# main_board_schematic.net
KiCad netlist of a schematic drawn in EasyEDA
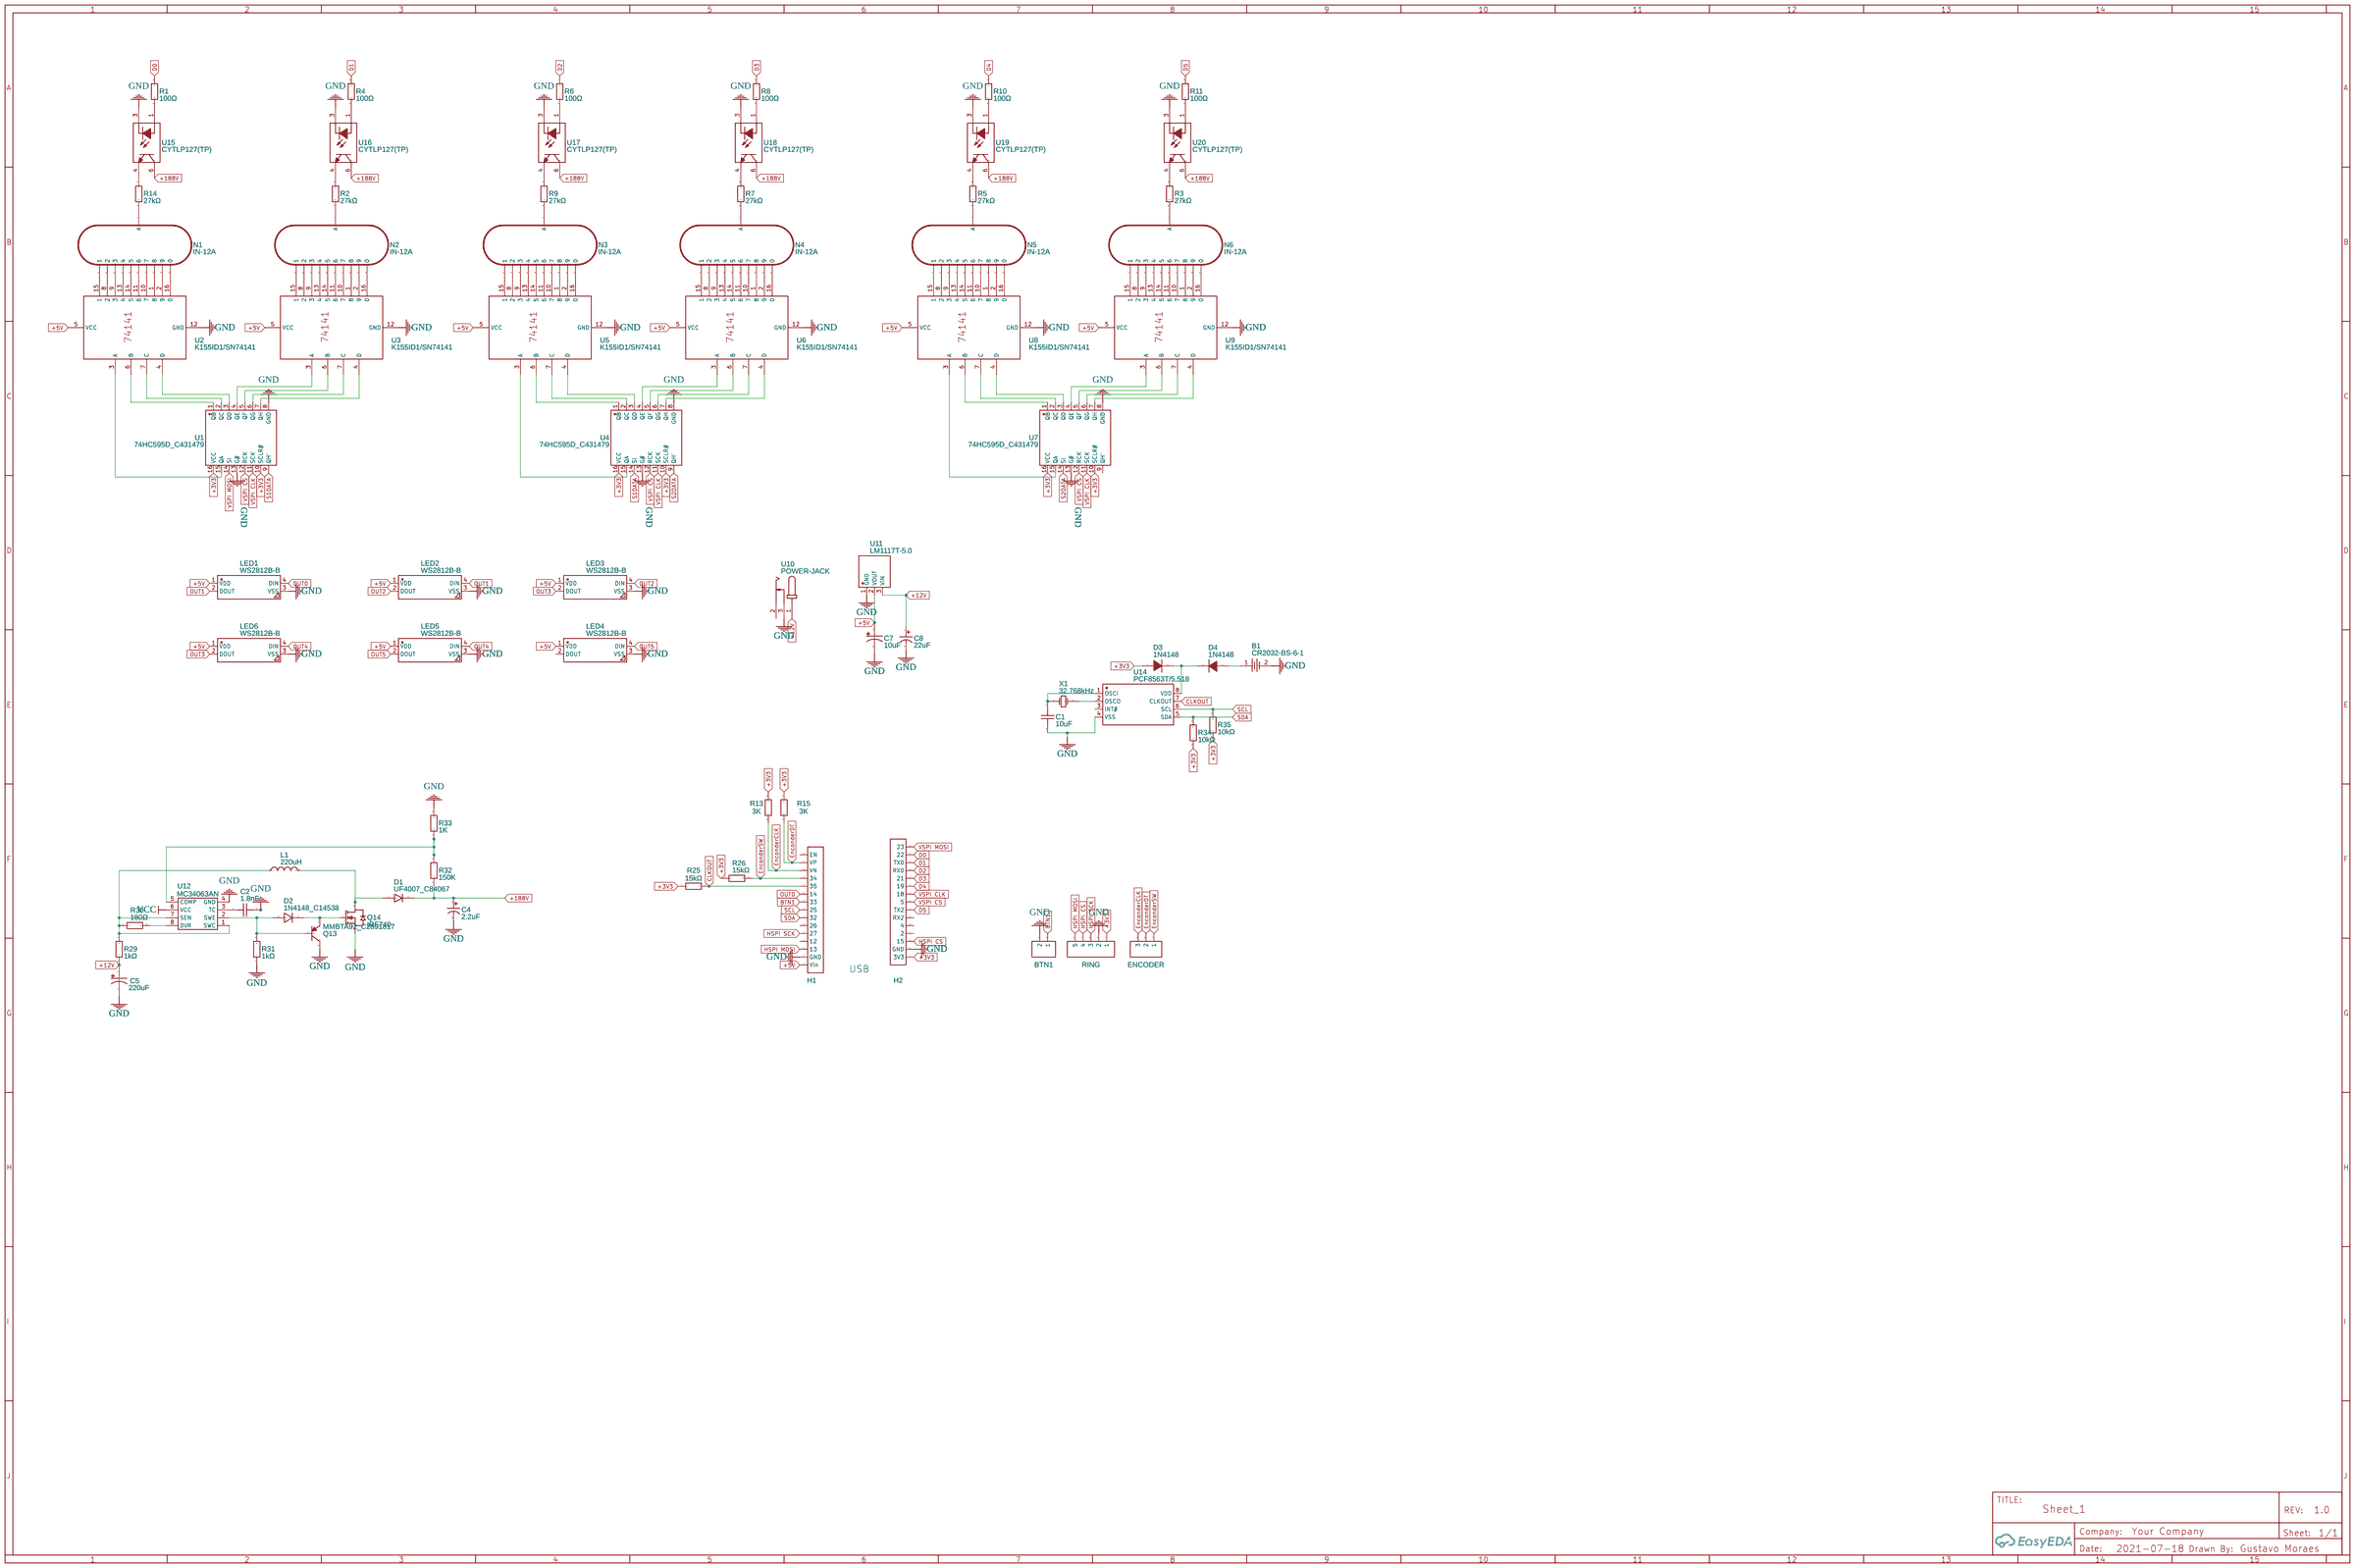
[diagram p0: schematic sheet]

(export (version "E")
  (design (tool "Eeschema 10.0.6"))
  (components
    (comp (ref "B1")
      (value "CR2032-BS-6-1")
      (fields (field (name "BOM_Supplier Part") "C70377"))
      (libsource (lib "") (part "CR2032-BS-6-1"))
    )
    (comp (ref "BTN1")
      (value "HDR-M-2.54_1x2")
      (fields (field (name "BOM_Supplier Part") "C124375"))
      (libsource (lib "") (part "HDR-M-2.54_1x2"))
    )
    (comp (ref "C1")
      (value "10uF")
      (fields
        (field (name "BOM_Manufacturer Part") "C0603X5R106K6R3NT")
        (field (name "BOM_Supplier Part") "C475250")
      )
      (libsource (lib "") (part "C0603X5R106K6R3NT"))
    )
    (comp (ref "C2")
      (value "1.8nF")
      (fields
        (field (name "BOM_Manufacturer Part") "NV1206B182K102CEDN")
        (field (name "BOM_Supplier Part") "C2760344")
      )
      (libsource (lib "") (part "NV1206B182K102CEDN"))
    )
    (comp (ref "C4")
      (value "2.2uF")
      (fields
        (field (name "BOM_Manufacturer Part") "UD2E2R2M0610")
        (field (name "BOM_Supplier Part") "C98559")
      )
      (libsource (lib "") (part "UD2E2R2M0610"))
    )
    (comp (ref "C5")
      (value "220uF")
      (fields
        (field (name "BOM_Manufacturer Part") "RT1E221M0810")
        (field (name "BOM_Supplier Part") "C280403")
      )
      (libsource (lib "") (part "RT1E221M0810"))
    )
    (comp (ref "C7")
      (value "10uF")
      (fields
        (field (name "BOM_Manufacturer Part") "UWX1C100MCL2GB")
        (field (name "BOM_Supplier Part") "C250999")
      )
      (libsource (lib "") (part "UWX1C100MCL2GB"))
    )
    (comp (ref "C8")
      (value "22uF")
      (fields
        (field (name "BOM_Manufacturer Part") "RVT1C220M0405")
        (field (name "BOM_Supplier Part") "C72502")
      )
      (libsource (lib "") (part "RVT1C220M0405"))
    )
    (comp (ref "D1")
      (value "UF4007_C84067")
      (fields (field (name "BOM_Manufacturer Part") "UF4007") (field (name "BOM_Supplier Part") "C84067"))
      (libsource (lib "") (part "UF4007_C84067"))
    )
    (comp (ref "D2")
      (value "1N4148_C14538")
      (fields (field (name "BOM_Manufacturer Part") "1N4148") (field (name "BOM_Supplier Part") "C14538"))
      (libsource (lib "") (part "1N4148_C14538"))
    )
    (comp (ref "D3")
      (value "1N4148")
      (fields (field (name "BOM_Supplier Part") "C14516"))
      (libsource (lib "") (part "1N4148"))
    )
    (comp (ref "D4")
      (value "1N4148")
      (fields (field (name "BOM_Supplier Part") "C14516"))
      (libsource (lib "") (part "1N4148_1"))
    )
    (comp (ref "ENCODER")
      (value "HDR-M-2.54_1x3")
      (fields (field (name "BOM_Supplier Part") "C180248"))
      (libsource (lib "") (part "HDR-M-2.54_1x3"))
    )
    (comp (ref "H1")
      (value "HDR-F-2.54_1x15")
      (fields (field (name "BOM_Supplier Part") "C124408"))
      (libsource (lib "") (part "HDR-F-2.54_1x15"))
    )
    (comp (ref "H2")
      (value "HDR-F-2.54_1x15")
      (fields (field (name "BOM_Supplier Part") "C124408"))
      (libsource (lib "") (part "HDR-F-2.54_1x15_1"))
    )
    (comp (ref "L1")
      (value "220uH")
      (fields
        (field (name "BOM_Manufacturer Part") "SLH1207S221MTT")
        (field (name "BOM_Supplier Part") "C182174")
      )
      (libsource (lib "") (part "SLH1207S221MTT"))
    )
    (comp (ref "LED1")
      (value "WS2812B-B")
      (fields (field (name "BOM_Supplier Part") "C114586"))
      (libsource (lib "") (part "WS2812B-B"))
    )
    (comp (ref "LED2")
      (value "WS2812B-B")
      (fields (field (name "BOM_Supplier Part") "C114586"))
      (libsource (lib "") (part "WS2812B-B"))
    )
    (comp (ref "LED3")
      (value "WS2812B-B")
      (fields (field (name "BOM_Supplier Part") "C114586"))
      (libsource (lib "") (part "WS2812B-B"))
    )
    (comp (ref "LED4")
      (value "WS2812B-B")
      (fields (field (name "BOM_Supplier Part") "C114586"))
      (libsource (lib "") (part "WS2812B-B"))
    )
    (comp (ref "LED5")
      (value "WS2812B-B")
      (fields (field (name "BOM_Supplier Part") "C114586"))
      (libsource (lib "") (part "WS2812B-B"))
    )
    (comp (ref "LED6")
      (value "WS2812B-B")
      (fields (field (name "BOM_Supplier Part") "C114586"))
      (libsource (lib "") (part "WS2812B-B"))
    )
    (comp (ref "N1") (value "IN-12A") (libsource (lib "") (part "IN-12A")))
    (comp (ref "N2") (value "IN-12A") (libsource (lib "") (part "IN-12A")))
    (comp (ref "N3") (value "IN-12A") (libsource (lib "") (part "IN-12A")))
    (comp (ref "N4") (value "IN-12A") (libsource (lib "") (part "IN-12A")))
    (comp (ref "N5") (value "IN-12A") (libsource (lib "") (part "IN-12A")))
    (comp (ref "N6") (value "IN-12A") (libsource (lib "") (part "IN-12A")))
    (comp (ref "Q13")
      (value "MMBTA92_C2891817")
      (fields (field (name "BOM_Manufacturer Part") "MMBTA92") (field (name "BOM_Supplier Part") "C2891817"))
      (libsource (lib "") (part "MMBTA92_C2891817"))
    )
    (comp (ref "Q14")
      (value "IRF740")
      (fields (field (name "BOM_Supplier Part") "C358408"))
      (libsource (lib "") (part "IRF740"))
    )
    (comp (ref "R1")
      (value "100Ω")
      (fields
        (field (name "BOM_Manufacturer Part") "AECR0805F100RK9")
        (field (name "BOM_Supplier Part") "C328380")
      )
      (libsource (lib "") (part "AECR0805F100RK9"))
    )
    (comp (ref "R2")
      (value "27kΩ")
      (fields
        (field (name "BOM_Manufacturer Part") "ARG06FTC2702")
        (field (name "BOM_Supplier Part") "C294144")
      )
      (libsource (lib "") (part "ARG06FTC2702"))
    )
    (comp (ref "R3")
      (value "27kΩ")
      (fields
        (field (name "BOM_Manufacturer Part") "ARG06FTC2702")
        (field (name "BOM_Supplier Part") "C294144")
      )
      (libsource (lib "") (part "ARG06FTC2702"))
    )
    (comp (ref "R4")
      (value "100Ω")
      (fields
        (field (name "BOM_Manufacturer Part") "AECR0805F100RK9")
        (field (name "BOM_Supplier Part") "C328380")
      )
      (libsource (lib "") (part "AECR0805F100RK9"))
    )
    (comp (ref "R5")
      (value "27kΩ")
      (fields
        (field (name "BOM_Manufacturer Part") "ARG06FTC2702")
        (field (name "BOM_Supplier Part") "C294144")
      )
      (libsource (lib "") (part "ARG06FTC2702"))
    )
    (comp (ref "R6")
      (value "100Ω")
      (fields
        (field (name "BOM_Manufacturer Part") "AECR0805F100RK9")
        (field (name "BOM_Supplier Part") "C328380")
      )
      (libsource (lib "") (part "AECR0805F100RK9"))
    )
    (comp (ref "R7")
      (value "27kΩ")
      (fields
        (field (name "BOM_Manufacturer Part") "ARG06FTC2702")
        (field (name "BOM_Supplier Part") "C294144")
      )
      (libsource (lib "") (part "ARG06FTC2702"))
    )
    (comp (ref "R8")
      (value "100Ω")
      (fields
        (field (name "BOM_Manufacturer Part") "AECR0805F100RK9")
        (field (name "BOM_Supplier Part") "C328380")
      )
      (libsource (lib "") (part "AECR0805F100RK9"))
    )
    (comp (ref "R9")
      (value "27kΩ")
      (fields
        (field (name "BOM_Manufacturer Part") "ARG06FTC2702")
        (field (name "BOM_Supplier Part") "C294144")
      )
      (libsource (lib "") (part "ARG06FTC2702"))
    )
    (comp (ref "R10")
      (value "100Ω")
      (fields
        (field (name "BOM_Manufacturer Part") "AECR0805F100RK9")
        (field (name "BOM_Supplier Part") "C328380")
      )
      (libsource (lib "") (part "AECR0805F100RK9"))
    )
    (comp (ref "R11")
      (value "100Ω")
      (fields
        (field (name "BOM_Manufacturer Part") "AECR0805F100RK9")
        (field (name "BOM_Supplier Part") "C328380")
      )
      (libsource (lib "") (part "AECR0805F100RK9"))
    )
    (comp (ref "R13")
      (value "3K")
      (fields
        (field (name "BOM_Manufacturer Part") "RC0805FR-073KL")
        (field (name "BOM_Supplier Part") "C126350")
      )
      (libsource (lib "") (part "RC0805FR-073KL"))
    )
    (comp (ref "R14")
      (value "27kΩ")
      (fields
        (field (name "BOM_Manufacturer Part") "ARG06FTC2702")
        (field (name "BOM_Supplier Part") "C294144")
      )
      (libsource (lib "") (part "ARG06FTC2702"))
    )
    (comp (ref "R15")
      (value "3K")
      (fields
        (field (name "BOM_Manufacturer Part") "RC0805FR-073KL")
        (field (name "BOM_Supplier Part") "C126350")
      )
      (libsource (lib "") (part "RC0805FR-073KL"))
    )
    (comp (ref "R25")
      (value "15kΩ")
      (fields
        (field (name "BOM_Manufacturer Part") "ERJ-6ENF1502V")
        (field (name "BOM_Supplier Part") "C192065")
      )
      (libsource (lib "") (part "ERJ-6ENF1502V"))
    )
    (comp (ref "R26")
      (value "15kΩ")
      (fields
        (field (name "BOM_Manufacturer Part") "ERJ-6ENF1502V")
        (field (name "BOM_Supplier Part") "C192065")
      )
      (libsource (lib "") (part "ERJ-6ENF1502V"))
    )
    (comp (ref "R29")
      (value "1kΩ")
      (fields
        (field (name "BOM_Manufacturer Part") "AECR1206F1K00K9")
        (field (name "BOM_Supplier Part") "C328410")
      )
      (libsource (lib "") (part "AECR1206F1K00K9"))
    )
    (comp (ref "R30")
      (value "180Ω")
      (fields
        (field (name "BOM_Manufacturer Part") "QR1206J180RP05")
        (field (name "BOM_Supplier Part") "C149884")
      )
      (libsource (lib "") (part "QR1206J180RP05"))
    )
    (comp (ref "R31")
      (value "1kΩ")
      (fields
        (field (name "BOM_Manufacturer Part") "AECR1206F1K00K9")
        (field (name "BOM_Supplier Part") "C328410")
      )
      (libsource (lib "") (part "AECR1206F1K00K9"))
    )
    (comp (ref "R32")
      (value "150K")
      (fields
        (field (name "BOM_Manufacturer Part") "MFR0W4F1503A50")
        (field (name "BOM_Supplier Part") "C58618")
      )
      (libsource (lib "") (part "MFR0W4F1503A50"))
    )
    (comp (ref "R33")
      (value "1K")
      (fields
        (field (name "BOM_Manufacturer Part") "MFR0W4F1001A50")
        (field (name "BOM_Supplier Part") "C57435")
      )
      (libsource (lib "") (part "MFR0W4F1001A50"))
    )
    (comp (ref "R34")
      (value "10kΩ")
      (fields
        (field (name "BOM_Manufacturer Part") "WR08X1002FTL")
        (field (name "BOM_Supplier Part") "C108451")
      )
      (libsource (lib "") (part "WR08X1002FTL"))
    )
    (comp (ref "R35")
      (value "10kΩ")
      (fields
        (field (name "BOM_Manufacturer Part") "WR08X1002FTL")
        (field (name "BOM_Supplier Part") "C108451")
      )
      (libsource (lib "") (part "WR08X1002FTL"))
    )
    (comp (ref "RING")
      (value "LED Ring")
      (fields (field (name "BOM_Supplier Part") "C358687"))
      (libsource (lib "") (part "HDR-M-2.54_1x5"))
    )
    (comp (ref "U1")
      (value "74HC595D_C431479")
      (fields (field (name "BOM_Manufacturer Part") "74HC595D") (field (name "BOM_Supplier Part") "C431479"))
      (libsource (lib "") (part "74HC595D_C431479"))
    )
    (comp (ref "U2") (value "K155ID1/SN74141") (libsource (lib "") (part "K155ID1/SN74141")))
    (comp (ref "U3") (value "K155ID1/SN74141") (libsource (lib "") (part "K155ID1/SN74141")))
    (comp (ref "U4")
      (value "74HC595D_C431479")
      (fields (field (name "BOM_Manufacturer Part") "74HC595D") (field (name "BOM_Supplier Part") "C431479"))
      (libsource (lib "") (part "74HC595D_C431479"))
    )
    (comp (ref "U5") (value "K155ID1/SN74141") (libsource (lib "") (part "K155ID1/SN74141")))
    (comp (ref "U6") (value "K155ID1/SN74141") (libsource (lib "") (part "K155ID1/SN74141")))
    (comp (ref "U7")
      (value "74HC595D_C431479")
      (fields (field (name "BOM_Manufacturer Part") "74HC595D") (field (name "BOM_Supplier Part") "C431479"))
      (libsource (lib "") (part "74HC595D_C431479"))
    )
    (comp (ref "U8") (value "K155ID1/SN74141") (libsource (lib "") (part "K155ID1/SN74141")))
    (comp (ref "U9") (value "K155ID1/SN74141") (libsource (lib "") (part "K155ID1/SN74141")))
    (comp (ref "U10")
      (value "POWER-JACK")
      (fields (field (name "BOM_Supplier Part") "C9900001795"))
      (libsource (lib "") (part "POWER-JACK"))
    )
    (comp (ref "U11")
      (value "LM1117T-5.0")
      (fields (field (name "BOM_Supplier Part") "C498320"))
      (libsource (lib "") (part "LM1117T-5.0"))
    )
    (comp (ref "U12")
      (value "MC34063AN")
      (fields (field (name "BOM_Supplier Part") "C126078"))
      (libsource (lib "") (part "MC34063AN"))
    )
    (comp (ref "U14")
      (value "PCF8563T/5,518")
      (fields (field (name "BOM_Supplier Part") "C7440"))
      (libsource (lib "") (part "PCF8563T/5,518"))
    )
    (comp (ref "U15")
      (value "CYTLP127(TP)")
      (fields (field (name "BOM_Supplier Part") "C2836429"))
      (libsource (lib "") (part "CYTLP127(TP)"))
    )
    (comp (ref "U16")
      (value "CYTLP127(TP)")
      (fields (field (name "BOM_Supplier Part") "C2836429"))
      (libsource (lib "") (part "CYTLP127(TP)"))
    )
    (comp (ref "U17")
      (value "CYTLP127(TP)")
      (fields (field (name "BOM_Supplier Part") "C2836429"))
      (libsource (lib "") (part "CYTLP127(TP)"))
    )
    (comp (ref "U18")
      (value "CYTLP127(TP)")
      (fields (field (name "BOM_Supplier Part") "C2836429"))
      (libsource (lib "") (part "CYTLP127(TP)"))
    )
    (comp (ref "U19")
      (value "CYTLP127(TP)")
      (fields (field (name "BOM_Supplier Part") "C2836429"))
      (libsource (lib "") (part "CYTLP127(TP)"))
    )
    (comp (ref "U20")
      (value "CYTLP127(TP)")
      (fields (field (name "BOM_Supplier Part") "C2836429"))
      (libsource (lib "") (part "CYTLP127(TP)"))
    )
    (comp (ref "X1")
      (value "32.768kHz")
      (fields
        (field (name "BOM_Manufacturer Part") "X206032768KGB2SC")
        (field (name "BOM_Supplier Part") "C2236")
      )
      (libsource (lib "") (part "X206032768KGB2SC"))
    )
  )
  (nets
    (net (code "1") (name "+3V3") (class "Default")
      (node (ref "D3") (pin "1") (pinfunction "A_1") (pintype "unspecified"))
      (node (ref "H2") (pin "1") (pinfunction "3V3_1") (pintype "unspecified"))
      (node (ref "R13") (pin "2") (pinfunction "2_2") (pintype "input"))
      (node (ref "R15") (pin "2") (pinfunction "2_2") (pintype "input"))
      (node (ref "R25") (pin "1") (pinfunction "1_1") (pintype "unspecified"))
      (node (ref "R26") (pin "1") (pinfunction "1_1") (pintype "unspecified"))
      (node (ref "R34") (pin "1") (pinfunction "1_1") (pintype "input"))
      (node (ref "R35") (pin "1") (pinfunction "1_1") (pintype "input"))
      (node (ref "RING") (pin "1") (pinfunction "1_1") (pintype "unspecified"))
      (node (ref "U1") (pin "10") (pinfunction "SCLR#_10") (pintype "unspecified"))
      (node (ref "U1") (pin "16") (pinfunction "VCC_16") (pintype "unspecified"))
      (node (ref "U4") (pin "10") (pinfunction "SCLR#_10") (pintype "unspecified"))
      (node (ref "U4") (pin "16") (pinfunction "VCC_16") (pintype "unspecified"))
      (node (ref "U7") (pin "10") (pinfunction "SCLR#_10") (pintype "unspecified"))
      (node (ref "U7") (pin "16") (pinfunction "VCC_16") (pintype "unspecified"))
    )
    (net (code "2") (name "+5V") (class "Default")
      (node (ref "C7") (pin "1") (pinfunction "1_1") (pintype "unspecified"))
      (node (ref "H1") (pin "1") (pinfunction "Vin_1") (pintype "unspecified"))
      (node (ref "LED1") (pin "1") (pinfunction "VDD_1") (pintype "unspecified"))
      (node (ref "LED2") (pin "1") (pinfunction "VDD_1") (pintype "unspecified"))
      (node (ref "LED3") (pin "1") (pinfunction "VDD_1") (pintype "unspecified"))
      (node (ref "LED4") (pin "1") (pinfunction "VDD_1") (pintype "unspecified"))
      (node (ref "LED5") (pin "1") (pinfunction "VDD_1") (pintype "unspecified"))
      (node (ref "LED6") (pin "1") (pinfunction "VDD_1") (pintype "unspecified"))
      (node (ref "U11") (pin "2") (pinfunction "VOUT_2") (pintype "unspecified"))
      (node (ref "U2") (pin "5") (pinfunction "VCC_5") (pintype "passive"))
      (node (ref "U3") (pin "5") (pinfunction "VCC_5") (pintype "passive"))
      (node (ref "U5") (pin "5") (pinfunction "VCC_5") (pintype "passive"))
      (node (ref "U6") (pin "5") (pinfunction "VCC_5") (pintype "passive"))
      (node (ref "U8") (pin "5") (pinfunction "VCC_5") (pintype "passive"))
      (node (ref "U9") (pin "5") (pinfunction "VCC_5") (pintype "passive"))
    )
    (net (code "3") (name "+12V") (class "Default")
      (node (ref "C5") (pin "1") (pinfunction "1_1") (pintype "unspecified"))
      (node (ref "C8") (pin "1") (pinfunction "1_1") (pintype "input"))
      (node (ref "R29") (pin "1") (pinfunction "1_1") (pintype "unspecified"))
      (node (ref "U10") (pin "1") (pinfunction "1_1") (pintype "unspecified"))
      (node (ref "U11") (pin "3") (pinfunction "VIN_3") (pintype "unspecified"))
    )
    (net (code "4") (name "+188V") (class "Default")
      (node (ref "C4") (pin "1") (pinfunction "1_1") (pintype "input"))
      (node (ref "D1") (pin "2") (pinfunction "C_2") (pintype "unspecified"))
      (node (ref "R32") (pin "1") (pinfunction "1_1") (pintype "input"))
      (node (ref "U15") (pin "6") (pinfunction "COL_6") (pintype "unspecified"))
      (node (ref "U16") (pin "6") (pinfunction "COL_6") (pintype "unspecified"))
      (node (ref "U17") (pin "6") (pinfunction "COL_6") (pintype "unspecified"))
      (node (ref "U18") (pin "6") (pinfunction "COL_6") (pintype "unspecified"))
      (node (ref "U19") (pin "6") (pinfunction "COL_6") (pintype "unspecified"))
      (node (ref "U20") (pin "6") (pinfunction "COL_6") (pintype "unspecified"))
    )
    (net (code "5") (name "BTN1") (class "Default")
      (node (ref "BTN1") (pin "1") (pinfunction "1_1") (pintype "unspecified"))
      (node (ref "H1") (pin "9") (pinfunction "33_9") (pintype "unspecified"))
    )
    (net (code "6") (name "CLKOUT") (class "Default")
      (node (ref "H1") (pin "11") (pinfunction "35_11") (pintype "unspecified"))
      (node (ref "R25") (pin "2") (pinfunction "2_2") (pintype "unspecified"))
      (node (ref "U14") (pin "7") (pinfunction "CLKOUT_7") (pintype "unspecified"))
    )
    (net (code "7") (name "D0") (class "Default")
      (node (ref "H2") (pin "14") (pinfunction "22_14") (pintype "unspecified"))
      (node (ref "R1") (pin "1") (pinfunction "1_1") (pintype "unspecified"))
    )
    (net (code "8") (name "D1") (class "Default")
      (node (ref "H2") (pin "13") (pinfunction "TX0_13") (pintype "unspecified"))
      (node (ref "R4") (pin "1") (pinfunction "1_1") (pintype "unspecified"))
    )
    (net (code "9") (name "D2") (class "Default")
      (node (ref "H2") (pin "12") (pinfunction "RX0_12") (pintype "unspecified"))
      (node (ref "R6") (pin "1") (pinfunction "1_1") (pintype "unspecified"))
    )
    (net (code "10") (name "D3") (class "Default")
      (node (ref "H2") (pin "11") (pinfunction "21_11") (pintype "unspecified"))
      (node (ref "R8") (pin "1") (pinfunction "1_1") (pintype "unspecified"))
    )
    (net (code "11") (name "D4") (class "Default")
      (node (ref "H2") (pin "10") (pinfunction "19_10") (pintype "unspecified"))
      (node (ref "R10") (pin "1") (pinfunction "1_1") (pintype "unspecified"))
    )
    (net (code "12") (name "D5") (class "Default")
      (node (ref "H2") (pin "7") (pinfunction "TX2_7") (pintype "unspecified"))
      (node (ref "R11") (pin "1") (pinfunction "1_1") (pintype "unspecified"))
    )
    (net (code "13") (name "EnconderCLK") (class "Default")
      (node (ref "ENCODER") (pin "3") (pinfunction "3_3") (pintype "input"))
      (node (ref "H1") (pin "13") (pinfunction "VN_13") (pintype "unspecified"))
      (node (ref "R13") (pin "1") (pinfunction "1_1") (pintype "input"))
    )
    (net (code "14") (name "EnconderDT") (class "Default")
      (node (ref "ENCODER") (pin "2") (pinfunction "2_2") (pintype "input"))
      (node (ref "H1") (pin "14") (pinfunction "VP_14") (pintype "unspecified"))
      (node (ref "R15") (pin "1") (pinfunction "1_1") (pintype "input"))
    )
    (net (code "15") (name "EnconderSW") (class "Default")
      (node (ref "ENCODER") (pin "1") (pinfunction "1_1") (pintype "input"))
      (node (ref "H1") (pin "12") (pinfunction "34_12") (pintype "unspecified"))
      (node (ref "R26") (pin "2") (pinfunction "2_2") (pintype "unspecified"))
    )
    (net (code "16") (name "GND") (class "Default")
      (node (ref "B1") (pin "2") (pinfunction "2_2") (pintype "input"))
      (node (ref "BTN1") (pin "2") (pinfunction "2_2") (pintype "unspecified"))
      (node (ref "C1") (pin "1") (pinfunction "1_1") (pintype "unspecified"))
      (node (ref "C2") (pin "2") (pinfunction "2_2") (pintype "unspecified"))
      (node (ref "C4") (pin "2") (pinfunction "2_2") (pintype "input"))
      (node (ref "C5") (pin "2") (pinfunction "2_2") (pintype "unspecified"))
      (node (ref "C7") (pin "2") (pinfunction "2_2") (pintype "unspecified"))
      (node (ref "C8") (pin "2") (pinfunction "2_2") (pintype "input"))
      (node (ref "H1") (pin "2") (pinfunction "GND_2") (pintype "unspecified"))
      (node (ref "H2") (pin "2") (pinfunction "GND_2") (pintype "unspecified"))
      (node (ref "LED1") (pin "3") (pinfunction "VSS_3") (pintype "unspecified"))
      (node (ref "LED2") (pin "3") (pinfunction "VSS_3") (pintype "unspecified"))
      (node (ref "LED3") (pin "3") (pinfunction "VSS_3") (pintype "unspecified"))
      (node (ref "LED4") (pin "3") (pinfunction "VSS_3") (pintype "unspecified"))
      (node (ref "LED5") (pin "3") (pinfunction "VSS_3") (pintype "unspecified"))
      (node (ref "LED6") (pin "3") (pinfunction "VSS_3") (pintype "unspecified"))
      (node (ref "Q13") (pin "3") (pinfunction "C_3") (pintype "input"))
      (node (ref "Q14") (pin "3") (pinfunction "S_3") (pintype "unspecified"))
      (node (ref "R31") (pin "1") (pinfunction "1_1") (pintype "unspecified"))
      (node (ref "R33") (pin "2") (pinfunction "2_2") (pintype "input"))
      (node (ref "RING") (pin "2") (pinfunction "2_2") (pintype "unspecified"))
      (node (ref "U1") (pin "13") (pinfunction "G#_13") (pintype "unspecified"))
      (node (ref "U1") (pin "8") (pinfunction "GND_8") (pintype "unspecified"))
      (node (ref "U10") (pin "3") (pinfunction "3_3") (pintype "unspecified"))
      (node (ref "U11") (pin "1") (pinfunction "GND_1") (pintype "unspecified"))
      (node (ref "U12") (pin "4") (pinfunction "GND_4") (pintype "unspecified"))
      (node (ref "U14") (pin "4") (pinfunction "VSS_4") (pintype "unspecified"))
      (node (ref "U15") (pin "3") (pinfunction "CAT_3") (pintype "unspecified"))
      (node (ref "U16") (pin "3") (pinfunction "CAT_3") (pintype "unspecified"))
      (node (ref "U17") (pin "3") (pinfunction "CAT_3") (pintype "unspecified"))
      (node (ref "U18") (pin "3") (pinfunction "CAT_3") (pintype "unspecified"))
      (node (ref "U19") (pin "3") (pinfunction "CAT_3") (pintype "unspecified"))
      (node (ref "U2") (pin "12") (pinfunction "GND_12") (pintype "passive"))
      (node (ref "U20") (pin "3") (pinfunction "CAT_3") (pintype "unspecified"))
      (node (ref "U3") (pin "12") (pinfunction "GND_12") (pintype "passive"))
      (node (ref "U4") (pin "13") (pinfunction "G#_13") (pintype "unspecified"))
      (node (ref "U4") (pin "8") (pinfunction "GND_8") (pintype "unspecified"))
      (node (ref "U5") (pin "12") (pinfunction "GND_12") (pintype "passive"))
      (node (ref "U6") (pin "12") (pinfunction "GND_12") (pintype "passive"))
      (node (ref "U7") (pin "13") (pinfunction "G#_13") (pintype "unspecified"))
      (node (ref "U7") (pin "8") (pinfunction "GND_8") (pintype "unspecified"))
      (node (ref "U8") (pin "12") (pinfunction "GND_12") (pintype "passive"))
      (node (ref "U9") (pin "12") (pinfunction "GND_12") (pintype "passive"))
    )
    (net (code "17") (name "HSPI CS") (class "Default")
      (node (ref "H2") (pin "3") (pinfunction "15_3") (pintype "unspecified"))
      (node (ref "RING") (pin "4") (pinfunction "4_4") (pintype "unspecified"))
    )
    (net (code "18") (name "HSPI MOSI") (class "Default")
      (node (ref "H1") (pin "3") (pinfunction "13_3") (pintype "unspecified"))
      (node (ref "RING") (pin "5") (pinfunction "5_5") (pintype "unspecified"))
    )
    (net (code "19") (name "HSPI SCK") (class "Default")
      (node (ref "H1") (pin "5") (pinfunction "27_5") (pintype "unspecified"))
      (node (ref "RING") (pin "3") (pinfunction "3_3") (pintype "unspecified"))
    )
    (net (code "20") (name "Net-(D1-A)") (class "Default")
      (node (ref "D1") (pin "1") (pinfunction "A_1") (pintype "unspecified"))
      (node (ref "L1") (pin "2") (pinfunction "2_2") (pintype "unspecified"))
      (node (ref "Q14") (pin "2") (pinfunction "D_2") (pintype "unspecified"))
    )
    (net (code "21") (name "Net-(D3-C)") (class "Default")
      (node (ref "D3") (pin "2") (pinfunction "C_2") (pintype "unspecified"))
      (node (ref "D4") (pin "2") (pinfunction "C_2") (pintype "unspecified"))
      (node (ref "U14") (pin "8") (pinfunction "VDD_8") (pintype "unspecified"))
    )
    (net (code "22") (name "Net-(D4-A)") (class "Default")
      (node (ref "B1") (pin "1") (pinfunction "1_1") (pintype "input"))
      (node (ref "D4") (pin "1") (pinfunction "A_1") (pintype "unspecified"))
    )
    (net (code "23") (name "Net-(N1-PadA)") (class "Default")
      (node (ref "N1") (pin "A") (pinfunction "A_A") (pintype "unspecified"))
      (node (ref "R14") (pin "1") (pinfunction "1_1") (pintype "unspecified"))
    )
    (net (code "24") (name "Net-(N2-PadA)") (class "Default")
      (node (ref "N2") (pin "A") (pinfunction "A_A") (pintype "unspecified"))
      (node (ref "R2") (pin "1") (pinfunction "1_1") (pintype "unspecified"))
    )
    (net (code "25") (name "Net-(N3-PadA)") (class "Default")
      (node (ref "N3") (pin "A") (pinfunction "A_A") (pintype "unspecified"))
      (node (ref "R9") (pin "1") (pinfunction "1_1") (pintype "unspecified"))
    )
    (net (code "26") (name "Net-(N4-PadA)") (class "Default")
      (node (ref "N4") (pin "A") (pinfunction "A_A") (pintype "unspecified"))
      (node (ref "R7") (pin "1") (pinfunction "1_1") (pintype "unspecified"))
    )
    (net (code "27") (name "Net-(N5-PadA)") (class "Default")
      (node (ref "N5") (pin "A") (pinfunction "A_A") (pintype "unspecified"))
      (node (ref "R5") (pin "1") (pinfunction "1_1") (pintype "unspecified"))
    )
    (net (code "28") (name "Net-(N6-PadA)") (class "Default")
      (node (ref "N6") (pin "A") (pinfunction "A_A") (pintype "unspecified"))
      (node (ref "R3") (pin "1") (pinfunction "1_1") (pintype "unspecified"))
    )
    (net (code "29") (name "Net-(Q13-B)") (class "Default")
      (node (ref "D2") (pin "2") (pinfunction "2_2") (pintype "unspecified"))
      (node (ref "Q13") (pin "1") (pinfunction "B_1") (pintype "input"))
      (node (ref "R31") (pin "2") (pinfunction "2_2") (pintype "unspecified"))
      (node (ref "U12") (pin "2") (pinfunction "SWE_2") (pintype "unspecified"))
    )
    (net (code "30") (name "Net-(Q13-E)") (class "Default")
      (node (ref "D2") (pin "1") (pinfunction "1_1") (pintype "unspecified"))
      (node (ref "Q13") (pin "2") (pinfunction "E_2") (pintype "input"))
      (node (ref "Q14") (pin "1") (pinfunction "G_1") (pintype "unspecified"))
    )
    (net (code "31") (name "Net-(U1-QA)") (class "Default")
      (node (ref "U1") (pin "15") (pinfunction "QA_15") (pintype "unspecified"))
      (node (ref "U2") (pin "3") (pinfunction "A_3") (pintype "input"))
    )
    (net (code "32") (name "Net-(U1-QB)") (class "Default")
      (node (ref "U1") (pin "1") (pinfunction "QB_1") (pintype "unspecified"))
      (node (ref "U2") (pin "6") (pinfunction "B_6") (pintype "input"))
    )
    (net (code "33") (name "Net-(U1-QC)") (class "Default")
      (node (ref "U1") (pin "2") (pinfunction "QC_2") (pintype "unspecified"))
      (node (ref "U2") (pin "7") (pinfunction "C_7") (pintype "input"))
    )
    (net (code "34") (name "Net-(U1-QD)") (class "Default")
      (node (ref "U1") (pin "3") (pinfunction "QD_3") (pintype "unspecified"))
      (node (ref "U2") (pin "4") (pinfunction "D_4") (pintype "input"))
    )
    (net (code "35") (name "Net-(U1-QE)") (class "Default")
      (node (ref "U1") (pin "4") (pinfunction "QE_4") (pintype "unspecified"))
      (node (ref "U3") (pin "3") (pinfunction "A_3") (pintype "input"))
    )
    (net (code "36") (name "Net-(U1-QF)") (class "Default")
      (node (ref "U1") (pin "5") (pinfunction "QF_5") (pintype "unspecified"))
      (node (ref "U3") (pin "6") (pinfunction "B_6") (pintype "input"))
    )
    (net (code "37") (name "Net-(U1-QG)") (class "Default")
      (node (ref "U1") (pin "6") (pinfunction "QG_6") (pintype "unspecified"))
      (node (ref "U3") (pin "7") (pinfunction "C_7") (pintype "input"))
    )
    (net (code "38") (name "Net-(U1-QH)") (class "Default")
      (node (ref "U1") (pin "7") (pinfunction "QH_7") (pintype "unspecified"))
      (node (ref "U3") (pin "4") (pinfunction "D_4") (pintype "input"))
    )
    (net (code "39") (name "Net-(U2-0)") (class "Default")
      (node (ref "N1") (pin "0") (pinfunction "0_0") (pintype "unspecified"))
      (node (ref "U2") (pin "16") (pinfunction "0_16") (pintype "output"))
    )
    (net (code "40") (name "Net-(U2-1)") (class "Default")
      (node (ref "N1") (pin "1") (pinfunction "1_1") (pintype "unspecified"))
      (node (ref "U2") (pin "15") (pinfunction "1_15") (pintype "output"))
    )
    (net (code "41") (name "Net-(U2-2)") (class "Default")
      (node (ref "N1") (pin "2") (pinfunction "2_2") (pintype "unspecified"))
      (node (ref "U2") (pin "8") (pinfunction "2_8") (pintype "output"))
    )
    (net (code "42") (name "Net-(U2-3)") (class "Default")
      (node (ref "N1") (pin "3") (pinfunction "3_3") (pintype "unspecified"))
      (node (ref "U2") (pin "9") (pinfunction "3_9") (pintype "output"))
    )
    (net (code "43") (name "Net-(U2-4)") (class "Default")
      (node (ref "N1") (pin "4") (pinfunction "4_4") (pintype "unspecified"))
      (node (ref "U2") (pin "13") (pinfunction "4_13") (pintype "output"))
    )
    (net (code "44") (name "Net-(U2-5)") (class "Default")
      (node (ref "N1") (pin "5") (pinfunction "5_5") (pintype "unspecified"))
      (node (ref "U2") (pin "14") (pinfunction "5_14") (pintype "output"))
    )
    (net (code "45") (name "Net-(U2-6)") (class "Default")
      (node (ref "N1") (pin "6") (pinfunction "6_6") (pintype "unspecified"))
      (node (ref "U2") (pin "11") (pinfunction "6_11") (pintype "output"))
    )
    (net (code "46") (name "Net-(U2-7)") (class "Default")
      (node (ref "N1") (pin "7") (pinfunction "7_7") (pintype "unspecified"))
      (node (ref "U2") (pin "10") (pinfunction "7_10") (pintype "output"))
    )
    (net (code "47") (name "Net-(U2-8)") (class "Default")
      (node (ref "N1") (pin "8") (pinfunction "8_8") (pintype "unspecified"))
      (node (ref "U2") (pin "1") (pinfunction "8_1") (pintype "output"))
    )
    (net (code "48") (name "Net-(U2-9)") (class "Default")
      (node (ref "N1") (pin "9") (pinfunction "9_9") (pintype "unspecified"))
      (node (ref "U2") (pin "2") (pinfunction "9_2") (pintype "output"))
    )
    (net (code "49") (name "Net-(U3-0)") (class "Default")
      (node (ref "N2") (pin "0") (pinfunction "0_0") (pintype "unspecified"))
      (node (ref "U3") (pin "16") (pinfunction "0_16") (pintype "output"))
    )
    (net (code "50") (name "Net-(U3-1)") (class "Default")
      (node (ref "N2") (pin "1") (pinfunction "1_1") (pintype "unspecified"))
      (node (ref "U3") (pin "15") (pinfunction "1_15") (pintype "output"))
    )
    (net (code "51") (name "Net-(U3-2)") (class "Default")
      (node (ref "N2") (pin "2") (pinfunction "2_2") (pintype "unspecified"))
      (node (ref "U3") (pin "8") (pinfunction "2_8") (pintype "output"))
    )
    (net (code "52") (name "Net-(U3-3)") (class "Default")
      (node (ref "N2") (pin "3") (pinfunction "3_3") (pintype "unspecified"))
      (node (ref "U3") (pin "9") (pinfunction "3_9") (pintype "output"))
    )
    (net (code "53") (name "Net-(U3-4)") (class "Default")
      (node (ref "N2") (pin "4") (pinfunction "4_4") (pintype "unspecified"))
      (node (ref "U3") (pin "13") (pinfunction "4_13") (pintype "output"))
    )
    (net (code "54") (name "Net-(U3-5)") (class "Default")
      (node (ref "N2") (pin "5") (pinfunction "5_5") (pintype "unspecified"))
      (node (ref "U3") (pin "14") (pinfunction "5_14") (pintype "output"))
    )
    (net (code "55") (name "Net-(U3-6)") (class "Default")
      (node (ref "N2") (pin "6") (pinfunction "6_6") (pintype "unspecified"))
      (node (ref "U3") (pin "11") (pinfunction "6_11") (pintype "output"))
    )
    (net (code "56") (name "Net-(U3-7)") (class "Default")
      (node (ref "N2") (pin "7") (pinfunction "7_7") (pintype "unspecified"))
      (node (ref "U3") (pin "10") (pinfunction "7_10") (pintype "output"))
    )
    (net (code "57") (name "Net-(U3-8)") (class "Default")
      (node (ref "N2") (pin "8") (pinfunction "8_8") (pintype "unspecified"))
      (node (ref "U3") (pin "1") (pinfunction "8_1") (pintype "output"))
    )
    (net (code "58") (name "Net-(U3-9)") (class "Default")
      (node (ref "N2") (pin "9") (pinfunction "9_9") (pintype "unspecified"))
      (node (ref "U3") (pin "2") (pinfunction "9_2") (pintype "output"))
    )
    (net (code "59") (name "Net-(U4-QA)") (class "Default")
      (node (ref "U4") (pin "15") (pinfunction "QA_15") (pintype "unspecified"))
      (node (ref "U5") (pin "3") (pinfunction "A_3") (pintype "input"))
    )
    (net (code "60") (name "Net-(U4-QB)") (class "Default")
      (node (ref "U4") (pin "1") (pinfunction "QB_1") (pintype "unspecified"))
      (node (ref "U5") (pin "6") (pinfunction "B_6") (pintype "input"))
    )
    (net (code "61") (name "Net-(U4-QC)") (class "Default")
      (node (ref "U4") (pin "2") (pinfunction "QC_2") (pintype "unspecified"))
      (node (ref "U5") (pin "7") (pinfunction "C_7") (pintype "input"))
    )
    (net (code "62") (name "Net-(U4-QD)") (class "Default")
      (node (ref "U4") (pin "3") (pinfunction "QD_3") (pintype "unspecified"))
      (node (ref "U5") (pin "4") (pinfunction "D_4") (pintype "input"))
    )
    (net (code "63") (name "Net-(U4-QE)") (class "Default")
      (node (ref "U4") (pin "4") (pinfunction "QE_4") (pintype "unspecified"))
      (node (ref "U6") (pin "3") (pinfunction "A_3") (pintype "input"))
    )
    (net (code "64") (name "Net-(U4-QF)") (class "Default")
      (node (ref "U4") (pin "5") (pinfunction "QF_5") (pintype "unspecified"))
      (node (ref "U6") (pin "6") (pinfunction "B_6") (pintype "input"))
    )
    (net (code "65") (name "Net-(U4-QG)") (class "Default")
      (node (ref "U4") (pin "6") (pinfunction "QG_6") (pintype "unspecified"))
      (node (ref "U6") (pin "7") (pinfunction "C_7") (pintype "input"))
    )
    (net (code "66") (name "Net-(U4-QH)") (class "Default")
      (node (ref "U4") (pin "7") (pinfunction "QH_7") (pintype "unspecified"))
      (node (ref "U6") (pin "4") (pinfunction "D_4") (pintype "input"))
    )
    (net (code "67") (name "Net-(U5-0)") (class "Default")
      (node (ref "N3") (pin "0") (pinfunction "0_0") (pintype "unspecified"))
      (node (ref "U5") (pin "16") (pinfunction "0_16") (pintype "output"))
    )
    (net (code "68") (name "Net-(U5-1)") (class "Default")
      (node (ref "N3") (pin "1") (pinfunction "1_1") (pintype "unspecified"))
      (node (ref "U5") (pin "15") (pinfunction "1_15") (pintype "output"))
    )
    (net (code "69") (name "Net-(U5-2)") (class "Default")
      (node (ref "N3") (pin "2") (pinfunction "2_2") (pintype "unspecified"))
      (node (ref "U5") (pin "8") (pinfunction "2_8") (pintype "output"))
    )
    (net (code "70") (name "Net-(U5-3)") (class "Default")
      (node (ref "N3") (pin "3") (pinfunction "3_3") (pintype "unspecified"))
      (node (ref "U5") (pin "9") (pinfunction "3_9") (pintype "output"))
    )
    (net (code "71") (name "Net-(U5-4)") (class "Default")
      (node (ref "N3") (pin "4") (pinfunction "4_4") (pintype "unspecified"))
      (node (ref "U5") (pin "13") (pinfunction "4_13") (pintype "output"))
    )
    (net (code "72") (name "Net-(U5-5)") (class "Default")
      (node (ref "N3") (pin "5") (pinfunction "5_5") (pintype "unspecified"))
      (node (ref "U5") (pin "14") (pinfunction "5_14") (pintype "output"))
    )
    (net (code "73") (name "Net-(U5-6)") (class "Default")
      (node (ref "N3") (pin "6") (pinfunction "6_6") (pintype "unspecified"))
      (node (ref "U5") (pin "11") (pinfunction "6_11") (pintype "output"))
    )
    (net (code "74") (name "Net-(U5-7)") (class "Default")
      (node (ref "N3") (pin "7") (pinfunction "7_7") (pintype "unspecified"))
      (node (ref "U5") (pin "10") (pinfunction "7_10") (pintype "output"))
    )
    (net (code "75") (name "Net-(U5-8)") (class "Default")
      (node (ref "N3") (pin "8") (pinfunction "8_8") (pintype "unspecified"))
      (node (ref "U5") (pin "1") (pinfunction "8_1") (pintype "output"))
    )
    (net (code "76") (name "Net-(U5-9)") (class "Default")
      (node (ref "N3") (pin "9") (pinfunction "9_9") (pintype "unspecified"))
      (node (ref "U5") (pin "2") (pinfunction "9_2") (pintype "output"))
    )
    (net (code "77") (name "Net-(U6-0)") (class "Default")
      (node (ref "N4") (pin "0") (pinfunction "0_0") (pintype "unspecified"))
      (node (ref "U6") (pin "16") (pinfunction "0_16") (pintype "output"))
    )
    (net (code "78") (name "Net-(U6-1)") (class "Default")
      (node (ref "N4") (pin "1") (pinfunction "1_1") (pintype "unspecified"))
      (node (ref "U6") (pin "15") (pinfunction "1_15") (pintype "output"))
    )
    (net (code "79") (name "Net-(U6-2)") (class "Default")
      (node (ref "N4") (pin "2") (pinfunction "2_2") (pintype "unspecified"))
      (node (ref "U6") (pin "8") (pinfunction "2_8") (pintype "output"))
    )
    (net (code "80") (name "Net-(U6-3)") (class "Default")
      (node (ref "N4") (pin "3") (pinfunction "3_3") (pintype "unspecified"))
      (node (ref "U6") (pin "9") (pinfunction "3_9") (pintype "output"))
    )
    (net (code "81") (name "Net-(U6-4)") (class "Default")
      (node (ref "N4") (pin "4") (pinfunction "4_4") (pintype "unspecified"))
      (node (ref "U6") (pin "13") (pinfunction "4_13") (pintype "output"))
    )
    (net (code "82") (name "Net-(U6-5)") (class "Default")
      (node (ref "N4") (pin "5") (pinfunction "5_5") (pintype "unspecified"))
      (node (ref "U6") (pin "14") (pinfunction "5_14") (pintype "output"))
    )
    (net (code "83") (name "Net-(U6-6)") (class "Default")
      (node (ref "N4") (pin "6") (pinfunction "6_6") (pintype "unspecified"))
      (node (ref "U6") (pin "11") (pinfunction "6_11") (pintype "output"))
    )
    (net (code "84") (name "Net-(U6-7)") (class "Default")
      (node (ref "N4") (pin "7") (pinfunction "7_7") (pintype "unspecified"))
      (node (ref "U6") (pin "10") (pinfunction "7_10") (pintype "output"))
    )
    (net (code "85") (name "Net-(U6-8)") (class "Default")
      (node (ref "N4") (pin "8") (pinfunction "8_8") (pintype "unspecified"))
      (node (ref "U6") (pin "1") (pinfunction "8_1") (pintype "output"))
    )
    (net (code "86") (name "Net-(U6-9)") (class "Default")
      (node (ref "N4") (pin "9") (pinfunction "9_9") (pintype "unspecified"))
      (node (ref "U6") (pin "2") (pinfunction "9_2") (pintype "output"))
    )
    (net (code "87") (name "Net-(U7-QA)") (class "Default")
      (node (ref "U7") (pin "15") (pinfunction "QA_15") (pintype "unspecified"))
      (node (ref "U8") (pin "3") (pinfunction "A_3") (pintype "input"))
    )
    (net (code "88") (name "Net-(U7-QB)") (class "Default")
      (node (ref "U7") (pin "1") (pinfunction "QB_1") (pintype "unspecified"))
      (node (ref "U8") (pin "6") (pinfunction "B_6") (pintype "input"))
    )
    (net (code "89") (name "Net-(U7-QC)") (class "Default")
      (node (ref "U7") (pin "2") (pinfunction "QC_2") (pintype "unspecified"))
      (node (ref "U8") (pin "7") (pinfunction "C_7") (pintype "input"))
    )
    (net (code "90") (name "Net-(U7-QD)") (class "Default")
      (node (ref "U7") (pin "3") (pinfunction "QD_3") (pintype "unspecified"))
      (node (ref "U8") (pin "4") (pinfunction "D_4") (pintype "input"))
    )
    (net (code "91") (name "Net-(U7-QE)") (class "Default")
      (node (ref "U7") (pin "4") (pinfunction "QE_4") (pintype "unspecified"))
      (node (ref "U9") (pin "3") (pinfunction "A_3") (pintype "input"))
    )
    (net (code "92") (name "Net-(U7-QF)") (class "Default")
      (node (ref "U7") (pin "5") (pinfunction "QF_5") (pintype "unspecified"))
      (node (ref "U9") (pin "6") (pinfunction "B_6") (pintype "input"))
    )
    (net (code "93") (name "Net-(U7-QG)") (class "Default")
      (node (ref "U7") (pin "6") (pinfunction "QG_6") (pintype "unspecified"))
      (node (ref "U9") (pin "7") (pinfunction "C_7") (pintype "input"))
    )
    (net (code "94") (name "Net-(U7-QH)") (class "Default")
      (node (ref "U7") (pin "7") (pinfunction "QH_7") (pintype "unspecified"))
      (node (ref "U9") (pin "4") (pinfunction "D_4") (pintype "input"))
    )
    (net (code "95") (name "Net-(U8-0)") (class "Default")
      (node (ref "N5") (pin "0") (pinfunction "0_0") (pintype "unspecified"))
      (node (ref "U8") (pin "16") (pinfunction "0_16") (pintype "output"))
    )
    (net (code "96") (name "Net-(U8-1)") (class "Default")
      (node (ref "N5") (pin "1") (pinfunction "1_1") (pintype "unspecified"))
      (node (ref "U8") (pin "15") (pinfunction "1_15") (pintype "output"))
    )
    (net (code "97") (name "Net-(U8-2)") (class "Default")
      (node (ref "N5") (pin "2") (pinfunction "2_2") (pintype "unspecified"))
      (node (ref "U8") (pin "8") (pinfunction "2_8") (pintype "output"))
    )
    (net (code "98") (name "Net-(U8-3)") (class "Default")
      (node (ref "N5") (pin "3") (pinfunction "3_3") (pintype "unspecified"))
      (node (ref "U8") (pin "9") (pinfunction "3_9") (pintype "output"))
    )
    (net (code "99") (name "Net-(U8-4)") (class "Default")
      (node (ref "N5") (pin "4") (pinfunction "4_4") (pintype "unspecified"))
      (node (ref "U8") (pin "13") (pinfunction "4_13") (pintype "output"))
    )
    (net (code "100") (name "Net-(U8-5)") (class "Default")
      (node (ref "N5") (pin "5") (pinfunction "5_5") (pintype "unspecified"))
      (node (ref "U8") (pin "14") (pinfunction "5_14") (pintype "output"))
    )
    (net (code "101") (name "Net-(U8-6)") (class "Default")
      (node (ref "N5") (pin "6") (pinfunction "6_6") (pintype "unspecified"))
      (node (ref "U8") (pin "11") (pinfunction "6_11") (pintype "output"))
    )
    (net (code "102") (name "Net-(U8-7)") (class "Default")
      (node (ref "N5") (pin "7") (pinfunction "7_7") (pintype "unspecified"))
      (node (ref "U8") (pin "10") (pinfunction "7_10") (pintype "output"))
    )
    (net (code "103") (name "Net-(U8-8)") (class "Default")
      (node (ref "N5") (pin "8") (pinfunction "8_8") (pintype "unspecified"))
      (node (ref "U8") (pin "1") (pinfunction "8_1") (pintype "output"))
    )
    (net (code "104") (name "Net-(U8-9)") (class "Default")
      (node (ref "N5") (pin "9") (pinfunction "9_9") (pintype "unspecified"))
      (node (ref "U8") (pin "2") (pinfunction "9_2") (pintype "output"))
    )
    (net (code "105") (name "Net-(U9-0)") (class "Default")
      (node (ref "N6") (pin "0") (pinfunction "0_0") (pintype "unspecified"))
      (node (ref "U9") (pin "16") (pinfunction "0_16") (pintype "output"))
    )
    (net (code "106") (name "Net-(U9-1)") (class "Default")
      (node (ref "N6") (pin "1") (pinfunction "1_1") (pintype "unspecified"))
      (node (ref "U9") (pin "15") (pinfunction "1_15") (pintype "output"))
    )
    (net (code "107") (name "Net-(U9-2)") (class "Default")
      (node (ref "N6") (pin "2") (pinfunction "2_2") (pintype "unspecified"))
      (node (ref "U9") (pin "8") (pinfunction "2_8") (pintype "output"))
    )
    (net (code "108") (name "Net-(U9-3)") (class "Default")
      (node (ref "N6") (pin "3") (pinfunction "3_3") (pintype "unspecified"))
      (node (ref "U9") (pin "9") (pinfunction "3_9") (pintype "output"))
    )
    (net (code "109") (name "Net-(U9-4)") (class "Default")
      (node (ref "N6") (pin "4") (pinfunction "4_4") (pintype "unspecified"))
      (node (ref "U9") (pin "13") (pinfunction "4_13") (pintype "output"))
    )
    (net (code "110") (name "Net-(U9-5)") (class "Default")
      (node (ref "N6") (pin "5") (pinfunction "5_5") (pintype "unspecified"))
      (node (ref "U9") (pin "14") (pinfunction "5_14") (pintype "output"))
    )
    (net (code "111") (name "Net-(U9-6)") (class "Default")
      (node (ref "N6") (pin "6") (pinfunction "6_6") (pintype "unspecified"))
      (node (ref "U9") (pin "11") (pinfunction "6_11") (pintype "output"))
    )
    (net (code "112") (name "Net-(U9-7)") (class "Default")
      (node (ref "N6") (pin "7") (pinfunction "7_7") (pintype "unspecified"))
      (node (ref "U9") (pin "10") (pinfunction "7_10") (pintype "output"))
    )
    (net (code "113") (name "Net-(U9-8)") (class "Default")
      (node (ref "N6") (pin "8") (pinfunction "8_8") (pintype "unspecified"))
      (node (ref "U9") (pin "1") (pinfunction "8_1") (pintype "output"))
    )
    (net (code "114") (name "Net-(U9-9)") (class "Default")
      (node (ref "N6") (pin "9") (pinfunction "9_9") (pintype "unspecified"))
      (node (ref "U9") (pin "2") (pinfunction "9_2") (pintype "output"))
    )
    (net (code "115") (name "Net-(U12-COMP)") (class "Default")
      (node (ref "R32") (pin "2") (pinfunction "2_2") (pintype "input"))
      (node (ref "R33") (pin "1") (pinfunction "1_1") (pintype "input"))
      (node (ref "U12") (pin "5") (pinfunction "COMP_5") (pintype "unspecified"))
    )
    (net (code "116") (name "Net-(U12-DVR)") (class "Default")
      (node (ref "R30") (pin "2") (pinfunction "2_2") (pintype "unspecified"))
      (node (ref "U12") (pin "8") (pinfunction "DVR_8") (pintype "unspecified"))
    )
    (net (code "117") (name "Net-(U12-SEN)") (class "Default")
      (node (ref "L1") (pin "1") (pinfunction "1_1") (pintype "unspecified"))
      (node (ref "R29") (pin "2") (pinfunction "2_2") (pintype "unspecified"))
      (node (ref "R30") (pin "1") (pinfunction "1_1") (pintype "unspecified"))
      (node (ref "U12") (pin "1") (pinfunction "SWC_1") (pintype "unspecified"))
      (node (ref "U12") (pin "7") (pinfunction "SEN_7") (pintype "unspecified"))
    )
    (net (code "118") (name "Net-(U12-TC)") (class "Default")
      (node (ref "C2") (pin "1") (pinfunction "1_1") (pintype "unspecified"))
      (node (ref "U12") (pin "3") (pinfunction "TC_3") (pintype "unspecified"))
    )
    (net (code "119") (name "Net-(U14-OSCI)") (class "Default")
      (node (ref "C1") (pin "2") (pinfunction "2_2") (pintype "unspecified"))
      (node (ref "U14") (pin "1") (pinfunction "OSCI_1") (pintype "unspecified"))
      (node (ref "X1") (pin "2") (pinfunction "OSC2_2") (pintype "unspecified"))
    )
    (net (code "120") (name "Net-(U14-OSCO)") (class "Default")
      (node (ref "U14") (pin "2") (pinfunction "OSCO_2") (pintype "unspecified"))
      (node (ref "X1") (pin "1") (pinfunction "OSC1_1") (pintype "unspecified"))
    )
    (net (code "121") (name "Net-(U15-AN)") (class "Default")
      (node (ref "R1") (pin "2") (pinfunction "2_2") (pintype "unspecified"))
      (node (ref "U15") (pin "1") (pinfunction "AN_1") (pintype "unspecified"))
    )
    (net (code "122") (name "Net-(U15-EM)") (class "Default")
      (node (ref "R14") (pin "2") (pinfunction "2_2") (pintype "unspecified"))
      (node (ref "U15") (pin "4") (pinfunction "EM_4") (pintype "unspecified"))
    )
    (net (code "123") (name "Net-(U16-AN)") (class "Default")
      (node (ref "R4") (pin "2") (pinfunction "2_2") (pintype "unspecified"))
      (node (ref "U16") (pin "1") (pinfunction "AN_1") (pintype "unspecified"))
    )
    (net (code "124") (name "Net-(U16-EM)") (class "Default")
      (node (ref "R2") (pin "2") (pinfunction "2_2") (pintype "unspecified"))
      (node (ref "U16") (pin "4") (pinfunction "EM_4") (pintype "unspecified"))
    )
    (net (code "125") (name "Net-(U17-AN)") (class "Default")
      (node (ref "R6") (pin "2") (pinfunction "2_2") (pintype "unspecified"))
      (node (ref "U17") (pin "1") (pinfunction "AN_1") (pintype "unspecified"))
    )
    (net (code "126") (name "Net-(U17-EM)") (class "Default")
      (node (ref "R9") (pin "2") (pinfunction "2_2") (pintype "unspecified"))
      (node (ref "U17") (pin "4") (pinfunction "EM_4") (pintype "unspecified"))
    )
    (net (code "127") (name "Net-(U18-AN)") (class "Default")
      (node (ref "R8") (pin "2") (pinfunction "2_2") (pintype "unspecified"))
      (node (ref "U18") (pin "1") (pinfunction "AN_1") (pintype "unspecified"))
    )
    (net (code "128") (name "Net-(U18-EM)") (class "Default")
      (node (ref "R7") (pin "2") (pinfunction "2_2") (pintype "unspecified"))
      (node (ref "U18") (pin "4") (pinfunction "EM_4") (pintype "unspecified"))
    )
    (net (code "129") (name "Net-(U19-AN)") (class "Default")
      (node (ref "R10") (pin "2") (pinfunction "2_2") (pintype "unspecified"))
      (node (ref "U19") (pin "1") (pinfunction "AN_1") (pintype "unspecified"))
    )
    (net (code "130") (name "Net-(U19-EM)") (class "Default")
      (node (ref "R5") (pin "2") (pinfunction "2_2") (pintype "unspecified"))
      (node (ref "U19") (pin "4") (pinfunction "EM_4") (pintype "unspecified"))
    )
    (net (code "131") (name "Net-(U20-AN)") (class "Default")
      (node (ref "R11") (pin "2") (pinfunction "2_2") (pintype "unspecified"))
      (node (ref "U20") (pin "1") (pinfunction "AN_1") (pintype "unspecified"))
    )
    (net (code "132") (name "Net-(U20-EM)") (class "Default")
      (node (ref "R3") (pin "2") (pinfunction "2_2") (pintype "unspecified"))
      (node (ref "U20") (pin "4") (pinfunction "EM_4") (pintype "unspecified"))
    )
    (net (code "133") (name "OUT0") (class "Default")
      (node (ref "H1") (pin "10") (pinfunction "14_10") (pintype "unspecified"))
      (node (ref "LED1") (pin "4") (pinfunction "DIN_4") (pintype "unspecified"))
    )
    (net (code "134") (name "OUT1") (class "Default")
      (node (ref "LED1") (pin "2") (pinfunction "DOUT_2") (pintype "unspecified"))
      (node (ref "LED2") (pin "4") (pinfunction "DIN_4") (pintype "unspecified"))
    )
    (net (code "135") (name "OUT2") (class "Default")
      (node (ref "LED2") (pin "2") (pinfunction "DOUT_2") (pintype "unspecified"))
      (node (ref "LED3") (pin "4") (pinfunction "DIN_4") (pintype "unspecified"))
    )
    (net (code "136") (name "OUT3") (class "Default")
      (node (ref "LED3") (pin "2") (pinfunction "DOUT_2") (pintype "unspecified"))
      (node (ref "LED6") (pin "2") (pinfunction "DOUT_2") (pintype "unspecified"))
    )
    (net (code "137") (name "OUT4") (class "Default")
      (node (ref "LED5") (pin "4") (pinfunction "DIN_4") (pintype "unspecified"))
      (node (ref "LED6") (pin "4") (pinfunction "DIN_4") (pintype "unspecified"))
    )
    (net (code "138") (name "OUT5") (class "Default")
      (node (ref "LED4") (pin "4") (pinfunction "DIN_4") (pintype "unspecified"))
      (node (ref "LED5") (pin "2") (pinfunction "DOUT_2") (pintype "unspecified"))
    )
    (net (code "139") (name "S1DATA") (class "Default")
      (node (ref "U1") (pin "9") (pinfunction "QH'_9") (pintype "unspecified"))
      (node (ref "U4") (pin "14") (pinfunction "SI_14") (pintype "unspecified"))
    )
    (net (code "140") (name "S2DATA") (class "Default")
      (node (ref "U4") (pin "9") (pinfunction "QH'_9") (pintype "unspecified"))
      (node (ref "U7") (pin "14") (pinfunction "SI_14") (pintype "unspecified"))
    )
    (net (code "141") (name "SCL") (class "Default")
      (node (ref "H1") (pin "8") (pinfunction "25_8") (pintype "unspecified"))
      (node (ref "R35") (pin "2") (pinfunction "2_2") (pintype "input"))
      (node (ref "U14") (pin "6") (pinfunction "SCL_6") (pintype "unspecified"))
    )
    (net (code "142") (name "SDA") (class "Default")
      (node (ref "H1") (pin "7") (pinfunction "32_7") (pintype "unspecified"))
      (node (ref "R34") (pin "2") (pinfunction "2_2") (pintype "input"))
      (node (ref "U14") (pin "5") (pinfunction "SDA_5") (pintype "unspecified"))
    )
    (net (code "143") (name "VCC") (class "Default")
      (node (ref "U12") (pin "6") (pinfunction "VCC_6") (pintype "unspecified"))
    )
    (net (code "144") (name "VSPI CLK") (class "Default")
      (node (ref "H2") (pin "9") (pinfunction "18_9") (pintype "unspecified"))
      (node (ref "U1") (pin "11") (pinfunction "SCK_11") (pintype "unspecified"))
      (node (ref "U4") (pin "11") (pinfunction "SCK_11") (pintype "unspecified"))
      (node (ref "U7") (pin "11") (pinfunction "SCK_11") (pintype "unspecified"))
    )
    (net (code "145") (name "VSPI CS") (class "Default")
      (node (ref "H2") (pin "8") (pinfunction "5_8") (pintype "unspecified"))
      (node (ref "U1") (pin "12") (pinfunction "RCK_12") (pintype "unspecified"))
      (node (ref "U4") (pin "12") (pinfunction "RCK_12") (pintype "unspecified"))
      (node (ref "U7") (pin "12") (pinfunction "RCK_12") (pintype "unspecified"))
    )
    (net (code "146") (name "VSPI MOSI") (class "Default")
      (node (ref "H2") (pin "15") (pinfunction "23_15") (pintype "unspecified"))
      (node (ref "U1") (pin "14") (pinfunction "SI_14") (pintype "unspecified"))
    )
    (net (code "147") (name "unconnected-(H1-12-Pad4)") (class "Default")
      (node (ref "H1") (pin "4") (pinfunction "12_4") (pintype "unspecified"))
    )
    (net (code "148") (name "unconnected-(H1-26-Pad6)") (class "Default")
      (node (ref "H1") (pin "6") (pinfunction "26_6") (pintype "unspecified"))
    )
    (net (code "149") (name "unconnected-(H1-EN-Pad15)") (class "Default")
      (node (ref "H1") (pin "15") (pinfunction "EN_15") (pintype "unspecified"))
    )
    (net (code "150") (name "unconnected-(H2-2-Pad4)") (class "Default")
      (node (ref "H2") (pin "4") (pinfunction "2_4") (pintype "unspecified"))
    )
    (net (code "151") (name "unconnected-(H2-4-Pad5)") (class "Default")
      (node (ref "H2") (pin "5") (pinfunction "4_5") (pintype "unspecified"))
    )
    (net (code "152") (name "unconnected-(H2-RX2-Pad6)") (class "Default")
      (node (ref "H2") (pin "6") (pinfunction "RX2_6") (pintype "unspecified"))
    )
    (net (code "153") (name "unconnected-(LED4-DOUT-Pad2)") (class "Default")
      (node (ref "LED4") (pin "2") (pinfunction "DOUT_2") (pintype "unspecified"))
    )
    (net (code "154") (name "unconnected-(U7-QH'-Pad9)") (class "Default")
      (node (ref "U7") (pin "9") (pinfunction "QH'_9") (pintype "unspecified"))
    )
    (net (code "155") (name "unconnected-(U10-Pad2)") (class "Default")
      (node (ref "U10") (pin "2") (pinfunction "2_2") (pintype "unspecified"))
    )
    (net (code "156") (name "unconnected-(U14-INT#-Pad3)") (class "Default")
      (node (ref "U14") (pin "3") (pinfunction "INT#_3") (pintype "unspecified"))
    )
  )
)
